# LiPoBBSupplyWithCharging.net
KiCad netlist of a schematic drawn in EAGLE
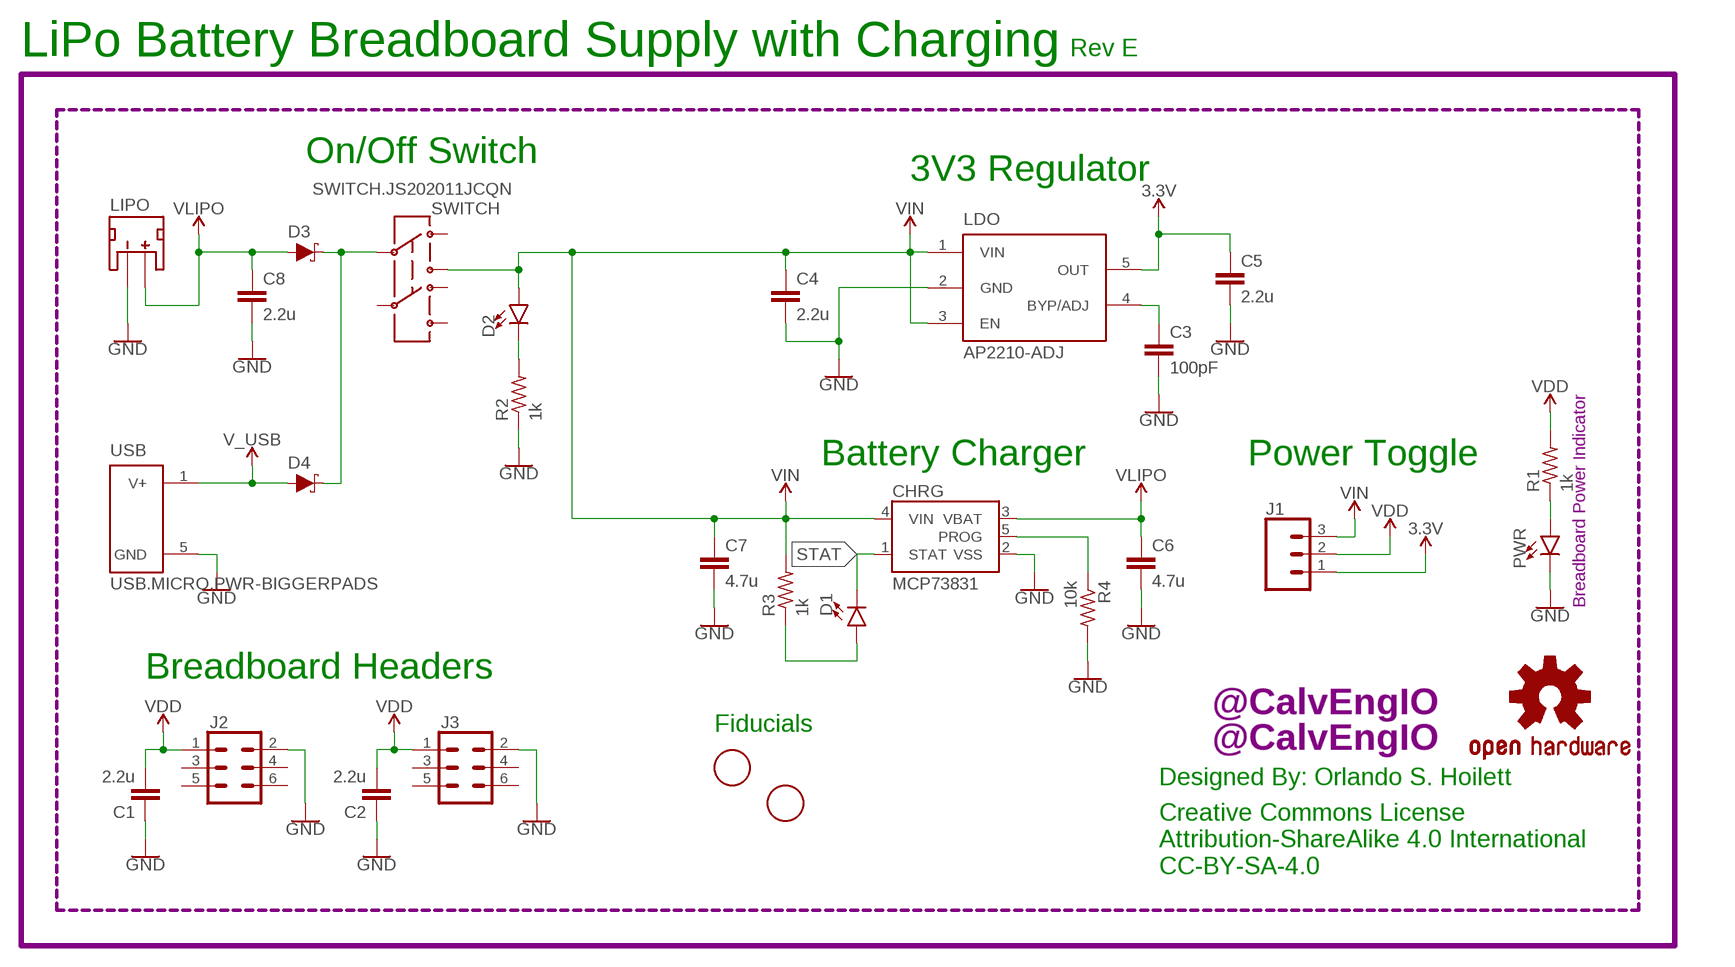
[diagram p0: schematic, sheet 1]

(export (version "E")
  (design (tool "Eeschema 10.0.6"))
  (components
    (comp (ref "C1")
      (value "2.2u")
      (footprint "eagle-import:C0603")
      (libsource (lib "eagle-import") (part "CAPACITOR0603"))
    )
    (comp (ref "C2")
      (value "2.2u")
      (footprint "eagle-import:C0603")
      (libsource (lib "eagle-import") (part "CAPACITOR0603"))
    )
    (comp (ref "C3")
      (value "100pF")
      (footprint "eagle-import:C0402")
      (libsource (lib "eagle-import") (part "C-EUC0402"))
    )
    (comp (ref "C4")
      (value "2.2u")
      (footprint "eagle-import:C0603")
      (libsource (lib "eagle-import") (part "CAPACITOR0603"))
    )
    (comp (ref "C5")
      (value "2.2u")
      (footprint "eagle-import:C0603")
      (libsource (lib "eagle-import") (part "CAPACITOR0603"))
    )
    (comp (ref "C6")
      (value "4.7u")
      (footprint "eagle-import:C0603")
      (libsource (lib "eagle-import") (part "CAPACITOR0603"))
    )
    (comp (ref "C7")
      (value "4.7u")
      (footprint "eagle-import:C0603")
      (libsource (lib "eagle-import") (part "CAPACITOR0603"))
    )
    (comp (ref "C8")
      (value "2.2u")
      (footprint "eagle-import:C0603")
      (libsource (lib "eagle-import") (part "CAPACITOR0603"))
    )
    (comp (ref "CHRG")
      (value "MCP73831")
      (footprint "eagle-import:SOT23-5")
      (libsource (lib "eagle-import") (part "MCP73831"))
    )
    (comp (ref "D1")
      (value "LED0603")
      (footprint "eagle-import:LED-0603")
      (libsource (lib "eagle-import") (part "LED0603"))
    )
    (comp (ref "D2")
      (value "LED0603")
      (footprint "eagle-import:LED-0603")
      (libsource (lib "eagle-import") (part "LED0603"))
    )
    (comp (ref "D3")
      (value "SCHOTTKY-USC")
      (footprint "eagle-import:USC")
      (libsource (lib "eagle-import") (part "SCHOTTKY-USC"))
    )
    (comp (ref "D4")
      (value "SCHOTTKY-USC")
      (footprint "eagle-import:USC")
      (libsource (lib "eagle-import") (part "SCHOTTKY-USC"))
    )
    (comp (ref "FD1")
      (value "FIDUCIAL")
      (footprint "eagle-import:FIDUCIAL_1MM")
      (libsource (lib "eagle-import") (part "FIDUCIAL"))
    )
    (comp (ref "FD2")
      (value "FIDUCIAL")
      (footprint "eagle-import:FIDUCIAL_1MM")
      (libsource (lib "eagle-import") (part "FIDUCIAL"))
    )
    (comp (ref "J1")
      (value "CONN_03")
      (footprint "eagle-import:1X03")
      (libsource (lib "eagle-import") (part "CONN_03"))
    )
    (comp (ref "J2")
      (value "CONN_03X22X3_SILK_MALE_PTH")
      (footprint "eagle-import:2X3")
      (libsource (lib "eagle-import") (part "CONN_03X22X3_SILK_MALE_PTH"))
    )
    (comp (ref "J3")
      (value "CONN_03X22X3_SILK_MALE_PTH")
      (footprint "eagle-import:2X3")
      (libsource (lib "eagle-import") (part "CONN_03X22X3_SILK_MALE_PTH"))
    )
    (comp (ref "LDO")
      (value "AP2210-ADJ")
      (footprint "eagle-import:SOT23-5")
      (libsource (lib "eagle-import") (part "AP2210-ADJ"))
    )
    (comp (ref "LIPO")
      (value "JST_2MM_MALE")
      (footprint "eagle-import:JST-2-SMD")
      (libsource (lib "eagle-import") (part "JST_2MM_MALE"))
    )
    (comp (ref "LOGO1")
      (value "OSHW-LOGOS")
      (footprint "eagle-import:OSHW-LOGO-S")
      (libsource (lib "eagle-import") (part "OSHW-LOGOS"))
    )
    (comp (ref "PWR")
      (value "LED0603")
      (footprint "eagle-import:LED-0603")
      (libsource (lib "eagle-import") (part "LED0603"))
    )
    (comp (ref "R1")
      (value "1k")
      (footprint "eagle-import:R0402")
      (libsource (lib "eagle-import") (part "R-US_R0402"))
    )
    (comp (ref "R2")
      (value "1k")
      (footprint "eagle-import:R0402")
      (libsource (lib "eagle-import") (part "RESISTOR0402"))
    )
    (comp (ref "R3")
      (value "1k")
      (footprint "eagle-import:R0402")
      (libsource (lib "eagle-import") (part "RESISTOR0402"))
    )
    (comp (ref "R4")
      (value "10k")
      (footprint "eagle-import:R0402")
      (libsource (lib "eagle-import") (part "RESISTOR0402"))
    )
    (comp (ref "SWITCH")
      (value "SWITCH.JS202011JCQN")
      (footprint "eagle-import:SWITCH.00")
      (libsource (lib "eagle-import") (part "SWITCH.JS202011JCQN"))
    )
    (comp (ref "U$1")
      (value "HANDLE.1HANDLE.025")
      (footprint "eagle-import:HANDLE.025")
      (libsource (lib "eagle-import") (part "HANDLE.1HANDLE.025"))
    )
    (comp (ref "U$3")
      (value "CALVENGIO_HANDLEHANDLE.1")
      (footprint "eagle-import:CALVENGIO_HANDLE.1")
      (libsource (lib "eagle-import") (part "CALVENGIO_HANDLEHANDLE.1"))
    )
    (comp (ref "USB")
      (value "USB.MICRO.PWR-BIGGERPADS")
      (footprint "eagle-import:USB-MICRO-01.BIGGERPADS.PWR")
      (libsource (lib "eagle-import") (part "USB.MICRO.PWR-BIGGERPADS"))
    )
  )
  (nets
    (net (code "1") (name "3.3V") (class "Default")
      (node (ref "C5") (pin "1") (pinfunction "1_1") (pintype "passive"))
      (node (ref "J1") (pin "1") (pinfunction "1_1") (pintype "passive"))
      (node (ref "LDO") (pin "5") (pinfunction "OUT_5") (pintype "bidirectional"))
    )
    (net (code "2") (name "GND") (class "Default")
      (node (ref "C1") (pin "1") (pinfunction "1_1") (pintype "passive"))
      (node (ref "C2") (pin "1") (pinfunction "1_1") (pintype "passive"))
      (node (ref "C3") (pin "2") (pinfunction "2_2") (pintype "passive"))
      (node (ref "C4") (pin "2") (pinfunction "2_2") (pintype "passive"))
      (node (ref "C5") (pin "2") (pinfunction "2_2") (pintype "passive"))
      (node (ref "C6") (pin "2") (pinfunction "2_2") (pintype "passive"))
      (node (ref "C7") (pin "2") (pinfunction "2_2") (pintype "passive"))
      (node (ref "C8") (pin "2") (pinfunction "2_2") (pintype "passive"))
      (node (ref "CHRG") (pin "2") (pinfunction "VSS_2") (pintype "power_in"))
      (node (ref "J2") (pin "2") (pinfunction "2_2") (pintype "bidirectional"))
      (node (ref "J3") (pin "2") (pinfunction "2_2") (pintype "bidirectional"))
      (node (ref "LDO") (pin "2") (pinfunction "GND_2") (pintype "bidirectional"))
      (node (ref "LIPO") (pin "1") (pinfunction "-_1") (pintype "bidirectional"))
      (node (ref "PWR") (pin "C") (pinfunction "C_C") (pintype "passive"))
      (node (ref "R2") (pin "1") (pinfunction "1_1") (pintype "passive"))
      (node (ref "R4") (pin "2") (pinfunction "2_2") (pintype "passive"))
      (node (ref "USB") (pin "5") (pinfunction "GND_5") (pintype "bidirectional"))
    )
    (net (code "3") (name "Net-(CHRG-PROG)") (class "Default")
      (node (ref "CHRG") (pin "5") (pinfunction "PROG_5") (pintype "input"))
      (node (ref "R4") (pin "1") (pinfunction "1_1") (pintype "passive"))
    )
    (net (code "4") (name "Net-(D1-PadA)") (class "Default")
      (node (ref "D1") (pin "A") (pinfunction "A_A") (pintype "passive"))
      (node (ref "R3") (pin "1") (pinfunction "1_1") (pintype "passive"))
    )
    (net (code "5") (name "Net-(D2-PadC)") (class "Default")
      (node (ref "D2") (pin "C") (pinfunction "C_C") (pintype "passive"))
      (node (ref "R2") (pin "2") (pinfunction "2_2") (pintype "passive"))
    )
    (net (code "6") (name "Net-(D3-C)") (class "Default")
      (node (ref "D3") (pin "-") (pinfunction "C_-") (pintype "passive"))
      (node (ref "D4") (pin "-") (pinfunction "C_-") (pintype "passive"))
      (node (ref "SWITCH") (pin "2") (pinfunction "2_2") (pintype "bidirectional"))
    )
    (net (code "7") (name "Net-(LDO-BYP{slash}ADJ)") (class "Default")
      (node (ref "C3") (pin "1") (pinfunction "1_1") (pintype "passive"))
      (node (ref "LDO") (pin "4") (pinfunction "BYP/ADJ_4") (pintype "bidirectional"))
    )
    (net (code "8") (name "Net-(PWR-PadA)") (class "Default")
      (node (ref "PWR") (pin "A") (pinfunction "A_A") (pintype "passive"))
      (node (ref "R1") (pin "1") (pinfunction "1_1") (pintype "passive"))
    )
    (net (code "9") (name "STAT") (class "Default")
      (node (ref "CHRG") (pin "1") (pinfunction "STAT_1") (pintype "output"))
      (node (ref "D1") (pin "C") (pinfunction "C_C") (pintype "passive"))
    )
    (net (code "10") (name "VDD") (class "Default")
      (node (ref "C1") (pin "2") (pinfunction "2_2") (pintype "passive"))
      (node (ref "C2") (pin "2") (pinfunction "2_2") (pintype "passive"))
      (node (ref "J1") (pin "2") (pinfunction "2_2") (pintype "passive"))
      (node (ref "J2") (pin "1") (pinfunction "1_1") (pintype "bidirectional"))
      (node (ref "J3") (pin "1") (pinfunction "1_1") (pintype "bidirectional"))
      (node (ref "R1") (pin "2") (pinfunction "2_2") (pintype "passive"))
    )
    (net (code "11") (name "VIN") (class "Default")
      (node (ref "C4") (pin "1") (pinfunction "1_1") (pintype "passive"))
      (node (ref "C7") (pin "1") (pinfunction "1_1") (pintype "passive"))
      (node (ref "CHRG") (pin "4") (pinfunction "VIN_4") (pintype "power_in"))
      (node (ref "D2") (pin "A") (pinfunction "A_A") (pintype "passive"))
      (node (ref "J1") (pin "3") (pinfunction "3_3") (pintype "passive"))
      (node (ref "LDO") (pin "1") (pinfunction "VIN_1") (pintype "bidirectional"))
      (node (ref "LDO") (pin "3") (pinfunction "EN_3") (pintype "bidirectional"))
      (node (ref "R3") (pin "2") (pinfunction "2_2") (pintype "passive"))
      (node (ref "SWITCH") (pin "3") (pinfunction "3_3") (pintype "bidirectional"))
    )
    (net (code "12") (name "VLIPO") (class "Default")
      (node (ref "C6") (pin "1") (pinfunction "1_1") (pintype "passive"))
      (node (ref "C8") (pin "1") (pinfunction "1_1") (pintype "passive"))
      (node (ref "CHRG") (pin "3") (pinfunction "VBAT_3") (pintype "power_in"))
      (node (ref "D3") (pin "+") (pinfunction "A_+") (pintype "passive"))
      (node (ref "LIPO") (pin "2") (pinfunction "+_2") (pintype "bidirectional"))
    )
    (net (code "13") (name "V_USB") (class "Default")
      (node (ref "D4") (pin "+") (pinfunction "A_+") (pintype "passive"))
      (node (ref "USB") (pin "1") (pinfunction "V+_1") (pintype "bidirectional"))
    )
    (net (code "14") (name "unconnected-(J2-Pad3)") (class "Default")
      (node (ref "J2") (pin "3") (pinfunction "3_3") (pintype "bidirectional"))
    )
    (net (code "15") (name "unconnected-(J2-Pad4)") (class "Default")
      (node (ref "J2") (pin "4") (pinfunction "4_4") (pintype "bidirectional"))
    )
    (net (code "16") (name "unconnected-(J2-Pad5)") (class "Default")
      (node (ref "J2") (pin "5") (pinfunction "5_5") (pintype "bidirectional"))
    )
    (net (code "17") (name "unconnected-(J2-Pad6)") (class "Default")
      (node (ref "J2") (pin "6") (pinfunction "6_6") (pintype "bidirectional"))
    )
    (net (code "18") (name "unconnected-(J3-Pad3)") (class "Default")
      (node (ref "J3") (pin "3") (pinfunction "3_3") (pintype "bidirectional"))
    )
    (net (code "19") (name "unconnected-(J3-Pad4)") (class "Default")
      (node (ref "J3") (pin "4") (pinfunction "4_4") (pintype "bidirectional"))
    )
    (net (code "20") (name "unconnected-(J3-Pad5)") (class "Default")
      (node (ref "J3") (pin "5") (pinfunction "5_5") (pintype "bidirectional"))
    )
    (net (code "21") (name "unconnected-(J3-Pad6)") (class "Default")
      (node (ref "J3") (pin "6") (pinfunction "6_6") (pintype "bidirectional"))
    )
    (net (code "22") (name "unconnected-(LIPO-PAD1-PadNC1)") (class "Default")
      (node (ref "LIPO") (pin "NC1") (pinfunction "PAD1_NC1") (pintype "bidirectional"))
    )
    (net (code "23") (name "unconnected-(LIPO-PAD2-PadNC2)") (class "Default")
      (node (ref "LIPO") (pin "NC2") (pinfunction "PAD2_NC2") (pintype "bidirectional"))
    )
    (net (code "24") (name "unconnected-(SWITCH-Pad1)") (class "Default")
      (node (ref "SWITCH") (pin "1") (pinfunction "1_1") (pintype "bidirectional"))
    )
    (net (code "25") (name "unconnected-(SWITCH-Pad5)") (class "Default")
      (node (ref "SWITCH") (pin "5") (pinfunction "5_5") (pintype "bidirectional"))
    )
    (net (code "26") (name "unconnected-(SWITCH-Pad6)") (class "Default")
      (node (ref "SWITCH") (pin "6") (pinfunction "6_6") (pintype "bidirectional"))
    )
    (net (code "27") (name "unconnected-(SWITCH-Pad7)") (class "Default")
      (node (ref "SWITCH") (pin "7") (pinfunction "7_7") (pintype "bidirectional"))
    )
  )
)
